# spot_welder.net
KiCad netlist of a schematic drawn in EAGLE
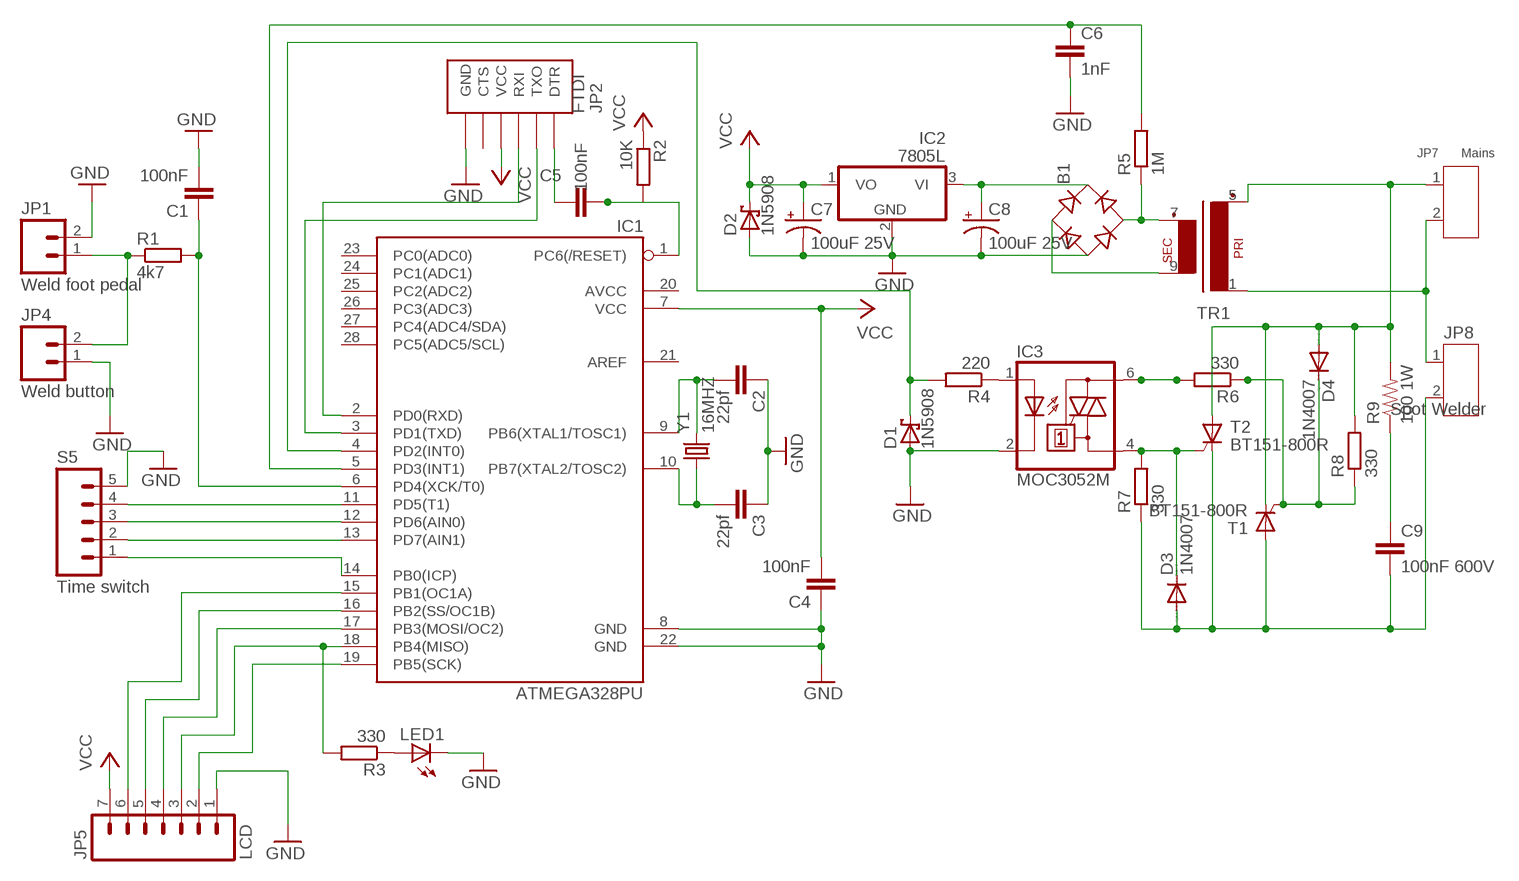
[diagram p0: schematic, sheet 1]

(export (version "E")
  (design (tool "Eeschema 10.0.6"))
  (components
    (comp (ref "B1")
      (value "B-DIL")
      (footprint "eagle-import:B-DIL")
      (libsource (lib "eagle-import") (part "B-DIL"))
    )
    (comp (ref "C1")
      (value "100nF")
      (footprint "eagle-import:CAP-PTH-5MM")
      (libsource (lib "eagle-import") (part "CAPPTH1"))
    )
    (comp (ref "C2")
      (value "22pf")
      (footprint "eagle-import:C025-024X044")
      (libsource (lib "eagle-import") (part "C-EU025-024X044"))
    )
    (comp (ref "C3")
      (value "22pf")
      (footprint "eagle-import:C025-024X044")
      (libsource (lib "eagle-import") (part "C-EU025-024X044"))
    )
    (comp (ref "C4")
      (value "100nF")
      (footprint "eagle-import:C025-024X044")
      (libsource (lib "eagle-import") (part "C-EU025-024X044"))
    )
    (comp (ref "C5")
      (value "100nF")
      (footprint "eagle-import:C025-024X044")
      (libsource (lib "eagle-import") (part "C-EU025-024X044"))
    )
    (comp (ref "C6")
      (value "1nF")
      (footprint "eagle-import:C025-024X044")
      (libsource (lib "eagle-import") (part "C-EU025-024X044"))
    )
    (comp (ref "C7")
      (value "100uF 25V")
      (footprint "eagle-import:CPOL-RADIAL-100UF-25V")
      (libsource (lib "eagle-import") (part "CAP_POLPTH1"))
    )
    (comp (ref "C8")
      (value "100uF 25V")
      (footprint "eagle-import:CPOL-RADIAL-100UF-25V")
      (libsource (lib "eagle-import") (part "CAP_POLPTH1"))
    )
    (comp (ref "C9")
      (value "100nF 600V")
      (footprint "eagle-import:C15B5")
      (libsource (lib "eagle-import") (part "C15/5"))
    )
    (comp (ref "D1")
      (value "1N5908")
      (footprint "eagle-import:C4111-15")
      (libsource (lib "eagle-import") (part "1N5908"))
    )
    (comp (ref "D2")
      (value "1N5908")
      (footprint "eagle-import:C4111-15")
      (libsource (lib "eagle-import") (part "1N5908"))
    )
    (comp (ref "D3")
      (value "1N4007")
      (footprint "eagle-import:DO41-10")
      (libsource (lib "eagle-import") (part "1N4004"))
    )
    (comp (ref "D4")
      (value "1N4007")
      (footprint "eagle-import:DO41-10")
      (libsource (lib "eagle-import") (part "1N4004"))
    )
    (comp (ref "IC1")
      (value "ATMEGA328PU")
      (footprint "eagle-import:DIL28-3")
      (libsource (lib "eagle-import") (part "ATMEGA328P_PDIP"))
    )
    (comp (ref "IC2")
      (value "7805L")
      (footprint "eagle-import:TO92")
      (libsource (lib "eagle-import") (part "78L05"))
    )
    (comp (ref "IC3")
      (value "MOC3052M")
      (footprint "eagle-import:DIL06")
      (fields (field (name "MF") "FAIRCHILD SEMICONDUCTOR") (field (name "MPN") "MOC3023-M"))
      (libsource (lib "eagle-import") (part "MOC30M23"))
    )
    (comp (ref "JP1")
      (value "Weld foot pedal")
      (footprint "eagle-import:1X02_LOCK")
      (libsource (lib "eagle-import") (part "M02LOCK"))
    )
    (comp (ref "JP2")
      (value "FTDI")
      (footprint "eagle-import:FTDI_DEVICE_SIDE")
      (libsource (lib "eagle-import") (part "FTDI_DEVICE"))
    )
    (comp (ref "JP4")
      (value "Weld button")
      (footprint "eagle-import:1X02_LOCK")
      (libsource (lib "eagle-import") (part "M02LOCK"))
    )
    (comp (ref "JP5")
      (value "LCD")
      (footprint "eagle-import:1X07_NO_SILK")
      (libsource (lib "eagle-import") (part "M07NO_SILK"))
    )
    (comp (ref "JP7")
      (value "Mains")
      (footprint "eagle-import:H2-5.0-10.5X8.0MM")
      (fields (field (name "MPN") "GSL009-5.0-02P-12"))
      (libsource (lib "eagle-import") (part "SCREW-TERMINAL-BLUE(2P-5.0)"))
    )
    (comp (ref "JP8")
      (value "Spot Welder")
      (footprint "eagle-import:H2-5.0-10.5X8.0MM")
      (fields (field (name "MPN") "GSL009-5.0-02P-12"))
      (libsource (lib "eagle-import") (part "SCREW-TERMINAL-BLUE(2P-5.0)"))
    )
    (comp (ref "LED1")
      (value "LEDLD260")
      (footprint "eagle-import:LD260")
      (libsource (lib "eagle-import") (part "LEDLD260"))
    )
    (comp (ref "R1")
      (value "4k7")
      (footprint "eagle-import:0204_7")
      (libsource (lib "eagle-import") (part "R-EU_0204/7"))
    )
    (comp (ref "R2")
      (value "10K")
      (footprint "eagle-import:0204_7")
      (libsource (lib "eagle-import") (part "R-EU_0204/7"))
    )
    (comp (ref "R3")
      (value "330")
      (footprint "eagle-import:0204_7")
      (libsource (lib "eagle-import") (part "R-EU_0204/7"))
    )
    (comp (ref "R4")
      (value "220")
      (footprint "eagle-import:0204_7")
      (libsource (lib "eagle-import") (part "R-EU_0204/7"))
    )
    (comp (ref "R5")
      (value "1M")
      (footprint "eagle-import:0204_7")
      (libsource (lib "eagle-import") (part "R-EU_0204/7"))
    )
    (comp (ref "R6")
      (value "330")
      (footprint "eagle-import:0204_7")
      (libsource (lib "eagle-import") (part "R-EU_0204/7"))
    )
    (comp (ref "R7")
      (value "330")
      (footprint "eagle-import:0204_7")
      (libsource (lib "eagle-import") (part "R-EU_0204/7"))
    )
    (comp (ref "R8")
      (value "330")
      (footprint "eagle-import:0204_7")
      (libsource (lib "eagle-import") (part "R-EU_0204/7"))
    )
    (comp (ref "R9")
      (value "100 1W")
      (footprint "eagle-import:AXIAL-0.6")
      (libsource (lib "eagle-import") (part "RESISTORPTH-1W"))
    )
    (comp (ref "S5")
      (value "Time switch")
      (footprint "eagle-import:1X05_NO_SILK")
      (libsource (lib "eagle-import") (part "M05NO_SILK"))
    )
    (comp (ref "T1")
      (value "BT151-800R")
      (footprint "eagle-import:TO220CS")
      (libsource (lib "eagle-import") (part "TIC126"))
    )
    (comp (ref "T2")
      (value "BT151-800R")
      (footprint "eagle-import:TO220CS")
      (libsource (lib "eagle-import") (part "TIC126"))
    )
    (comp (ref "TR1")
      (value "EI30-1")
      (footprint "eagle-import:EI30-1")
      (libsource (lib "eagle-import") (part "EI30-1"))
    )
    (comp (ref "Y1")
      (value "16MHZ")
      (footprint "eagle-import:HC49_S")
      (libsource (lib "eagle-import") (part "CRYSTALHC49S"))
    )
  )
  (nets
    (net (code "1") (name "GND") (class "Default")
      (node (ref "B1") (pin "-") (pinfunction "-_-") (pintype "passive"))
      (node (ref "C1") (pin "2") (pinfunction "2_2") (pintype "passive"))
      (node (ref "C2") (pin "1") (pinfunction "1_1") (pintype "passive"))
      (node (ref "C3") (pin "1") (pinfunction "1_1") (pintype "passive"))
      (node (ref "C4") (pin "1") (pinfunction "1_1") (pintype "passive"))
      (node (ref "C6") (pin "2") (pinfunction "2_2") (pintype "passive"))
      (node (ref "C7") (pin "2") (pinfunction "-_2") (pintype "passive"))
      (node (ref "C8") (pin "2") (pinfunction "-_2") (pintype "passive"))
      (node (ref "D1") (pin "A") (pinfunction "A_A") (pintype "passive"))
      (node (ref "D2") (pin "A") (pinfunction "A_A") (pintype "passive"))
      (node (ref "IC1") (pin "22") (pinfunction "GND_22") (pintype "bidirectional"))
      (node (ref "IC1") (pin "8") (pinfunction "GND_8") (pintype "bidirectional"))
      (node (ref "IC2") (pin "2") (pinfunction "GND_2") (pintype "passive"))
      (node (ref "IC3") (pin "2") (pinfunction "C_2") (pintype "passive"))
      (node (ref "JP1") (pin "2") (pinfunction "2_2") (pintype "passive"))
      (node (ref "JP2") (pin "P$6") (pinfunction "GND_P$6") (pintype "bidirectional"))
      (node (ref "JP4") (pin "1") (pinfunction "1_1") (pintype "passive"))
      (node (ref "JP5") (pin "1") (pinfunction "1_1") (pintype "passive"))
      (node (ref "LED1") (pin "K") (pinfunction "C_K") (pintype "passive"))
      (node (ref "S5") (pin "5") (pinfunction "5_5") (pintype "passive"))
    )
    (net (code "2") (name "Net-(C8-+)") (class "Default")
      (node (ref "B1") (pin "+") (pinfunction "+_+") (pintype "passive"))
      (node (ref "C8") (pin "1") (pinfunction "+_1") (pintype "passive"))
      (node (ref "IC2") (pin "3") (pinfunction "VI_3") (pintype "input"))
    )
    (net (code "3") (name "Net-(C9-Pad2)") (class "Default")
      (node (ref "C9") (pin "2") (pinfunction "2_2") (pintype "passive"))
      (node (ref "D3") (pin "A") (pinfunction "A_A") (pintype "passive"))
      (node (ref "JP8") (pin "2") (pinfunction "2_2") (pintype "bidirectional"))
      (node (ref "R7") (pin "1") (pinfunction "1_1") (pintype "passive"))
      (node (ref "T1") (pin "A") (pinfunction "A_A") (pintype "passive"))
      (node (ref "T2") (pin "C") (pinfunction "C_C") (pintype "passive"))
    )
    (net (code "4") (name "Net-(D4-PadC)") (class "Default")
      (node (ref "D4") (pin "C") (pinfunction "C_C") (pintype "passive"))
      (node (ref "R6") (pin "1") (pinfunction "1_1") (pintype "passive"))
      (node (ref "R8") (pin "1") (pinfunction "1_1") (pintype "passive"))
      (node (ref "T1") (pin "G") (pinfunction "G_G") (pintype "passive"))
    )
    (net (code "5") (name "Net-(IC1-PB0(ICP))") (class "Default")
      (node (ref "IC1") (pin "14") (pinfunction "PB0(ICP)_14") (pintype "bidirectional"))
      (node (ref "S5") (pin "1") (pinfunction "1_1") (pintype "passive"))
    )
    (net (code "6") (name "Net-(IC1-PB1(OC1A))") (class "Default")
      (node (ref "IC1") (pin "15") (pinfunction "PB1(OC1A)_15") (pintype "bidirectional"))
      (node (ref "JP5") (pin "6") (pinfunction "6_6") (pintype "passive"))
    )
    (net (code "7") (name "Net-(IC1-PB2(SS{slash}OC1B))") (class "Default")
      (node (ref "IC1") (pin "16") (pinfunction "PB2(SS/OC1B)_16") (pintype "bidirectional"))
      (node (ref "JP5") (pin "5") (pinfunction "5_5") (pintype "passive"))
    )
    (net (code "8") (name "Net-(IC1-PB3(MOSI{slash}OC2))") (class "Default")
      (node (ref "IC1") (pin "17") (pinfunction "PB3(MOSI/OC2)_17") (pintype "bidirectional"))
      (node (ref "JP5") (pin "4") (pinfunction "4_4") (pintype "passive"))
    )
    (net (code "9") (name "Net-(IC1-PB4(MISO))") (class "Default")
      (node (ref "IC1") (pin "18") (pinfunction "PB4(MISO)_18") (pintype "bidirectional"))
      (node (ref "JP5") (pin "3") (pinfunction "3_3") (pintype "passive"))
      (node (ref "R3") (pin "2") (pinfunction "2_2") (pintype "passive"))
    )
    (net (code "10") (name "Net-(IC1-PB5(SCK))") (class "Default")
      (node (ref "IC1") (pin "19") (pinfunction "PB5(SCK)_19") (pintype "bidirectional"))
      (node (ref "JP5") (pin "2") (pinfunction "2_2") (pintype "passive"))
    )
    (net (code "11") (name "Net-(IC1-PB6(XTAL1{slash}TOSC1))") (class "Default")
      (node (ref "C2") (pin "2") (pinfunction "2_2") (pintype "passive"))
      (node (ref "IC1") (pin "9") (pinfunction "PB6(XTAL1/TOSC1)_9") (pintype "bidirectional"))
      (node (ref "Y1") (pin "2") (pinfunction "2_2") (pintype "passive"))
    )
    (net (code "12") (name "Net-(IC1-PB7(XTAL2{slash}TOSC2))") (class "Default")
      (node (ref "C3") (pin "2") (pinfunction "2_2") (pintype "passive"))
      (node (ref "IC1") (pin "10") (pinfunction "PB7(XTAL2/TOSC2)_10") (pintype "bidirectional"))
      (node (ref "Y1") (pin "1") (pinfunction "1_1") (pintype "passive"))
    )
    (net (code "13") (name "Net-(IC1-PC6({slash}RESET))") (class "Default")
      (node (ref "C5") (pin "2") (pinfunction "2_2") (pintype "passive"))
      (node (ref "IC1") (pin "1") (pinfunction "PC6(/RESET)_1") (pintype "bidirectional"))
      (node (ref "R2") (pin "2") (pinfunction "2_2") (pintype "passive"))
    )
    (net (code "14") (name "Net-(IC1-PD0(RXD))") (class "Default")
      (node (ref "IC1") (pin "2") (pinfunction "PD0(RXD)_2") (pintype "bidirectional"))
      (node (ref "JP2") (pin "P$3") (pinfunction "RXI_P$3") (pintype "bidirectional"))
    )
    (net (code "15") (name "Net-(IC1-PD1(TXD))") (class "Default")
      (node (ref "IC1") (pin "3") (pinfunction "PD1(TXD)_3") (pintype "bidirectional"))
      (node (ref "JP2") (pin "P$2") (pinfunction "TXO_P$2") (pintype "bidirectional"))
    )
    (net (code "16") (name "Net-(IC1-PD2(INT0))") (class "Default")
      (node (ref "D1") (pin "C") (pinfunction "C_C") (pintype "passive"))
      (node (ref "IC1") (pin "4") (pinfunction "PD2(INT0)_4") (pintype "bidirectional"))
      (node (ref "R4") (pin "2") (pinfunction "2_2") (pintype "passive"))
    )
    (net (code "17") (name "Net-(IC1-PD3(INT1))") (class "Default")
      (node (ref "C6") (pin "1") (pinfunction "1_1") (pintype "passive"))
      (node (ref "IC1") (pin "5") (pinfunction "PD3(INT1)_5") (pintype "bidirectional"))
      (node (ref "R5") (pin "2") (pinfunction "2_2") (pintype "passive"))
    )
    (net (code "18") (name "Net-(IC1-PD4(XCK{slash}T0))") (class "Default")
      (node (ref "C1") (pin "1") (pinfunction "1_1") (pintype "passive"))
      (node (ref "IC1") (pin "6") (pinfunction "PD4(XCK/T0)_6") (pintype "bidirectional"))
      (node (ref "R1") (pin "2") (pinfunction "2_2") (pintype "passive"))
    )
    (net (code "19") (name "Net-(IC1-PD5(T1))") (class "Default")
      (node (ref "IC1") (pin "11") (pinfunction "PD5(T1)_11") (pintype "bidirectional"))
      (node (ref "S5") (pin "4") (pinfunction "4_4") (pintype "passive"))
    )
    (net (code "20") (name "Net-(IC1-PD6(AIN0))") (class "Default")
      (node (ref "IC1") (pin "12") (pinfunction "PD6(AIN0)_12") (pintype "bidirectional"))
      (node (ref "S5") (pin "3") (pinfunction "3_3") (pintype "passive"))
    )
    (net (code "21") (name "Net-(IC1-PD7(AIN1))") (class "Default")
      (node (ref "IC1") (pin "13") (pinfunction "PD7(AIN1)_13") (pintype "bidirectional"))
      (node (ref "S5") (pin "2") (pinfunction "2_2") (pintype "passive"))
    )
    (net (code "22") (name "Net-(IC3-A)") (class "Default")
      (node (ref "IC3") (pin "1") (pinfunction "A_1") (pintype "passive"))
      (node (ref "R4") (pin "1") (pinfunction "1_1") (pintype "passive"))
    )
    (net (code "23") (name "Net-(IC3-A1)") (class "Default")
      (node (ref "D3") (pin "C") (pinfunction "C_C") (pintype "passive"))
      (node (ref "IC3") (pin "4") (pinfunction "A1_4") (pintype "passive"))
      (node (ref "R7") (pin "2") (pinfunction "2_2") (pintype "passive"))
      (node (ref "T2") (pin "G") (pinfunction "G_G") (pintype "passive"))
    )
    (net (code "24") (name "Net-(IC3-A2)") (class "Default")
      (node (ref "IC3") (pin "6") (pinfunction "A2_6") (pintype "passive"))
      (node (ref "R6") (pin "2") (pinfunction "2_2") (pintype "passive"))
    )
    (net (code "25") (name "Net-(JP1-Pad1)") (class "Default")
      (node (ref "JP1") (pin "1") (pinfunction "1_1") (pintype "passive"))
      (node (ref "JP4") (pin "2") (pinfunction "2_2") (pintype "passive"))
      (node (ref "R1") (pin "1") (pinfunction "1_1") (pintype "passive"))
    )
    (net (code "26") (name "Net-(JP2-DTR)") (class "Default")
      (node (ref "C5") (pin "1") (pinfunction "1_1") (pintype "passive"))
      (node (ref "JP2") (pin "P$1") (pinfunction "DTR_P$1") (pintype "bidirectional"))
    )
    (net (code "27") (name "Net-(LED1-PadA)") (class "Default")
      (node (ref "LED1") (pin "A") (pinfunction "A_A") (pintype "passive"))
      (node (ref "R3") (pin "1") (pinfunction "1_1") (pintype "passive"))
    )
    (net (code "28") (name "Net-(R9-1)") (class "Default")
      (node (ref "C9") (pin "1") (pinfunction "1_1") (pintype "passive"))
      (node (ref "R9") (pin "P$1") (pinfunction "1_P$1") (pintype "passive"))
    )
    (net (code "29") (name "Net-(R9-2)") (class "Default")
      (node (ref "D4") (pin "A") (pinfunction "A_A") (pintype "passive"))
      (node (ref "JP7") (pin "1") (pinfunction "1_1") (pintype "bidirectional"))
      (node (ref "R8") (pin "2") (pinfunction "2_2") (pintype "passive"))
      (node (ref "R9") (pin "P$2") (pinfunction "2_P$2") (pintype "passive"))
      (node (ref "T1") (pin "C") (pinfunction "C_C") (pintype "passive"))
      (node (ref "T2") (pin "A") (pinfunction "A_A") (pintype "passive"))
      (node (ref "TR1") (pin "5") (pinfunction "P2_5") (pintype "passive"))
    )
    (net (code "30") (name "Net-(TR1-P1)") (class "Default")
      (node (ref "JP7") (pin "2") (pinfunction "2_2") (pintype "bidirectional"))
      (node (ref "JP8") (pin "1") (pinfunction "1_1") (pintype "bidirectional"))
      (node (ref "TR1") (pin "1") (pinfunction "P1_1") (pintype "passive"))
    )
    (net (code "31") (name "Net-(TR1-S3)") (class "Default")
      (node (ref "B1") (pin "AC2") (pinfunction "AC2_AC2") (pintype "passive"))
      (node (ref "R5") (pin "1") (pinfunction "1_1") (pintype "passive"))
      (node (ref "TR1") (pin "7") (pinfunction "S3_7") (pintype "passive"))
    )
    (net (code "32") (name "Net-(TR1-S4)") (class "Default")
      (node (ref "B1") (pin "AC1") (pinfunction "AC1_AC1") (pintype "passive"))
      (node (ref "TR1") (pin "9") (pinfunction "S4_9") (pintype "passive"))
    )
    (net (code "33") (name "VCC") (class "Default")
      (node (ref "C4") (pin "2") (pinfunction "2_2") (pintype "passive"))
      (node (ref "C7") (pin "1") (pinfunction "+_1") (pintype "passive"))
      (node (ref "D2") (pin "C") (pinfunction "C_C") (pintype "passive"))
      (node (ref "IC1") (pin "7") (pinfunction "VCC_7") (pintype "bidirectional"))
      (node (ref "IC2") (pin "1") (pinfunction "VO_1") (pintype "passive"))
      (node (ref "JP2") (pin "P$4") (pinfunction "VCC_P$4") (pintype "bidirectional"))
      (node (ref "JP5") (pin "7") (pinfunction "7_7") (pintype "passive"))
      (node (ref "R2") (pin "1") (pinfunction "1_1") (pintype "passive"))
    )
    (net (code "34") (name "unconnected-(IC1-AREF-Pad21)") (class "Default")
      (node (ref "IC1") (pin "21") (pinfunction "AREF_21") (pintype "bidirectional"))
    )
    (net (code "35") (name "unconnected-(IC1-AVCC-Pad20)") (class "Default")
      (node (ref "IC1") (pin "20") (pinfunction "AVCC_20") (pintype "bidirectional"))
    )
    (net (code "36") (name "unconnected-(IC1-PC0(ADC0)-Pad23)") (class "Default")
      (node (ref "IC1") (pin "23") (pinfunction "PC0(ADC0)_23") (pintype "bidirectional"))
    )
    (net (code "37") (name "unconnected-(IC1-PC1(ADC1)-Pad24)") (class "Default")
      (node (ref "IC1") (pin "24") (pinfunction "PC1(ADC1)_24") (pintype "bidirectional"))
    )
    (net (code "38") (name "unconnected-(IC1-PC2(ADC2)-Pad25)") (class "Default")
      (node (ref "IC1") (pin "25") (pinfunction "PC2(ADC2)_25") (pintype "bidirectional"))
    )
    (net (code "39") (name "unconnected-(IC1-PC3(ADC3)-Pad26)") (class "Default")
      (node (ref "IC1") (pin "26") (pinfunction "PC3(ADC3)_26") (pintype "bidirectional"))
    )
    (net (code "40") (name "unconnected-(IC1-PC4(ADC4{slash}SDA)-Pad27)") (class "Default")
      (node (ref "IC1") (pin "27") (pinfunction "PC4(ADC4/SDA)_27") (pintype "bidirectional"))
    )
    (net (code "41") (name "unconnected-(IC1-PC5(ADC5{slash}SCL)-Pad28)") (class "Default")
      (node (ref "IC1") (pin "28") (pinfunction "PC5(ADC5/SCL)_28") (pintype "bidirectional"))
    )
    (net (code "42") (name "unconnected-(JP2-CTS-PadP$5)") (class "Default")
      (node (ref "JP2") (pin "P$5") (pinfunction "CTS_P$5") (pintype "bidirectional"))
    )
  )
)
